# Project_Canary_V4_3.net
KiCad netlist of a schematic drawn in EAGLE
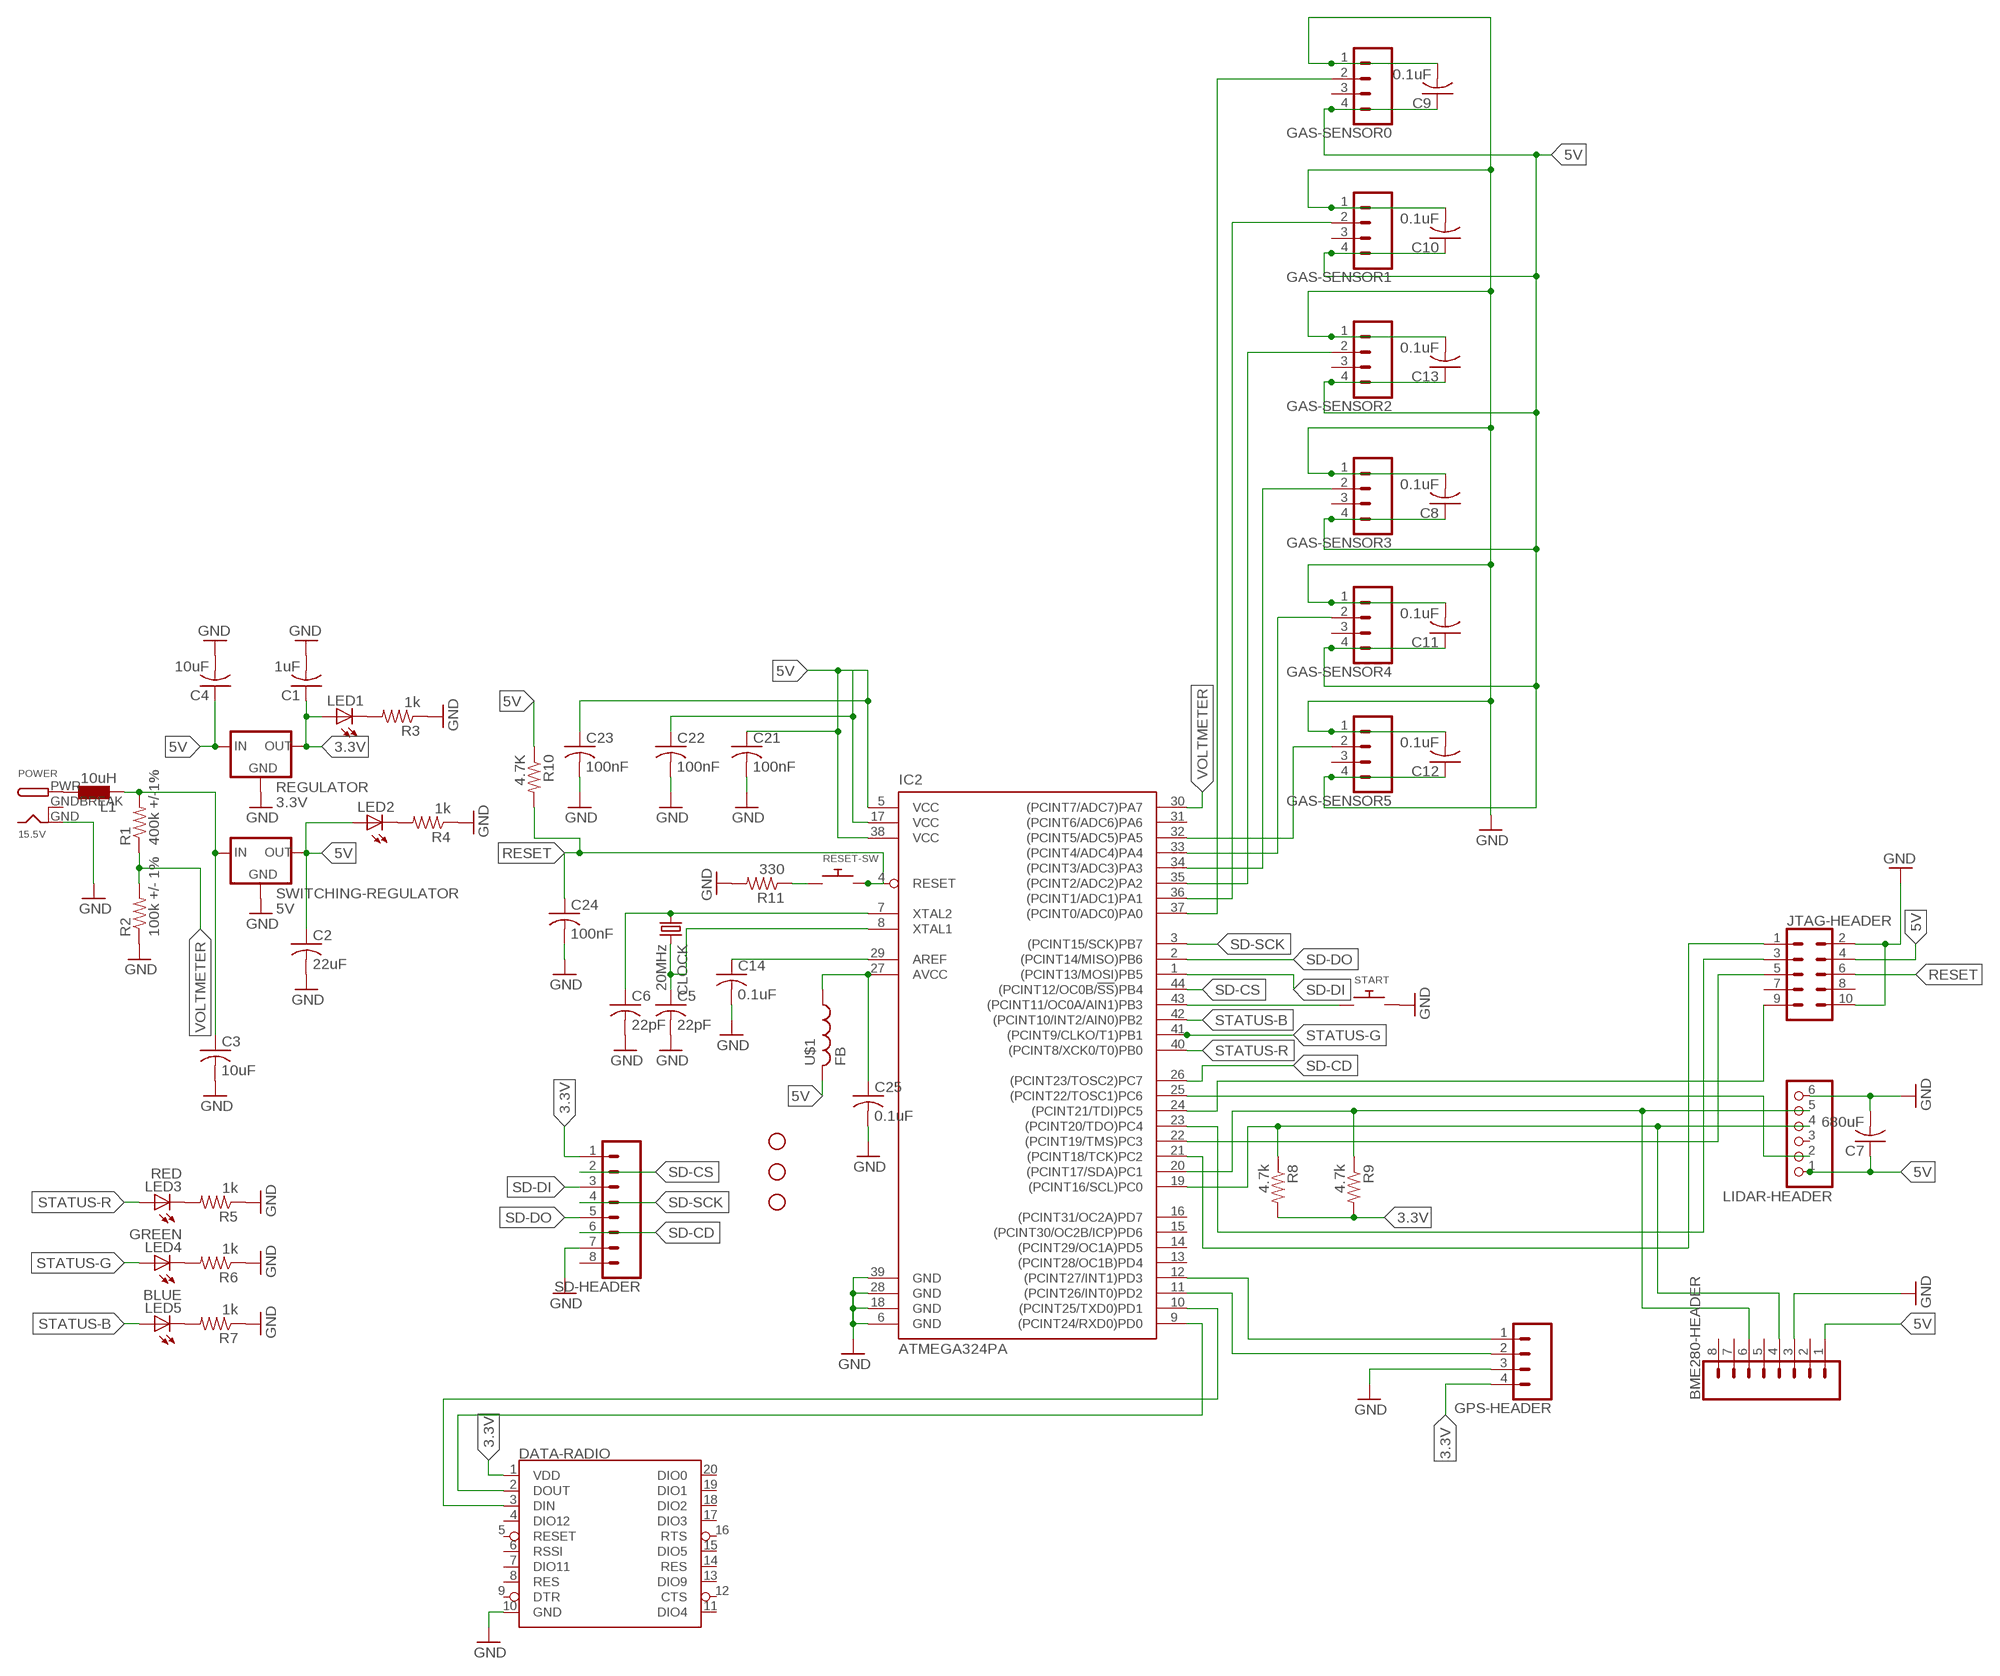
[diagram p0: schematic, sheet 1]

(export (version "E")
  (design (tool "Eeschema 10.0.6"))
  (components
    (comp (ref "BME280-HEADER")
      (value "CONN_08\"")
      (footprint "eagle-import:1X08")
      (libsource (lib "eagle-import") (part "CONN_08{dblquote}"))
    )
    (comp (ref "C1")
      (value "1uF")
      (footprint "eagle-import:C0805")
      (libsource (lib "eagle-import") (part "C-USC0805"))
    )
    (comp (ref "C2")
      (value "22uF")
      (footprint "eagle-import:C0603")
      (libsource (lib "eagle-import") (part "C-USC0603"))
    )
    (comp (ref "C3")
      (value "10uF")
      (footprint "eagle-import:C0805")
      (libsource (lib "eagle-import") (part "C-USC0805"))
    )
    (comp (ref "C4")
      (value "10uF")
      (footprint "eagle-import:C0603")
      (libsource (lib "eagle-import") (part "C-USC0603"))
    )
    (comp (ref "C5")
      (value "22pF")
      (footprint "eagle-import:C0603")
      (libsource (lib "eagle-import") (part "C-USC0603"))
    )
    (comp (ref "C6")
      (value "22pF")
      (footprint "eagle-import:C0603")
      (libsource (lib "eagle-import") (part "C-USC0603"))
    )
    (comp (ref "C7")
      (value "680uF")
      (footprint "eagle-import:C0603")
      (libsource (lib "eagle-import") (part "C-USC0603"))
    )
    (comp (ref "C8")
      (value "0.1uF")
      (footprint "eagle-import:C0603")
      (libsource (lib "eagle-import") (part "C-USC0603"))
    )
    (comp (ref "C9")
      (value "0.1uF")
      (footprint "eagle-import:C0603")
      (libsource (lib "eagle-import") (part "C-USC0603"))
    )
    (comp (ref "C10")
      (value "0.1uF")
      (footprint "eagle-import:C0603")
      (libsource (lib "eagle-import") (part "C-USC0603"))
    )
    (comp (ref "C11")
      (value "0.1uF")
      (footprint "eagle-import:C0603")
      (libsource (lib "eagle-import") (part "C-USC0603"))
    )
    (comp (ref "C12")
      (value "0.1uF")
      (footprint "eagle-import:C0603")
      (libsource (lib "eagle-import") (part "C-USC0603"))
    )
    (comp (ref "C13")
      (value "0.1uF")
      (footprint "eagle-import:C0603")
      (libsource (lib "eagle-import") (part "C-USC0603"))
    )
    (comp (ref "C14")
      (value "0.1uF")
      (footprint "eagle-import:C0603")
      (libsource (lib "eagle-import") (part "C-USC0603"))
    )
    (comp (ref "C21")
      (value "100nF")
      (footprint "eagle-import:C0603")
      (libsource (lib "eagle-import") (part "C-USC0603"))
    )
    (comp (ref "C22")
      (value "100nF")
      (footprint "eagle-import:C0603")
      (libsource (lib "eagle-import") (part "C-USC0603"))
    )
    (comp (ref "C23")
      (value "100nF")
      (footprint "eagle-import:C0603")
      (libsource (lib "eagle-import") (part "C-USC0603"))
    )
    (comp (ref "C24")
      (value "100nF")
      (footprint "eagle-import:C0805")
      (libsource (lib "eagle-import") (part "C-USC0805"))
    )
    (comp (ref "C25")
      (value "0.1uF")
      (footprint "eagle-import:C0603")
      (libsource (lib "eagle-import") (part "C-USC0603"))
    )
    (comp (ref "CLOCK")
      (value "20MHz")
      (footprint "eagle-import:86SMX")
      (libsource (lib "eagle-import") (part "CRYSTAL68SMX"))
    )
    (comp (ref "DATA-RADIO")
      (value "XBEE")
      (footprint "eagle-import:XBEE")
      (libsource (lib "eagle-import") (part "XBEE"))
    )
    (comp (ref "GAS-SENSOR0")
      (value "CONN_04")
      (footprint "eagle-import:1X04")
      (libsource (lib "eagle-import") (part "CONN_04"))
    )
    (comp (ref "GAS-SENSOR1")
      (value "CONN_04")
      (footprint "eagle-import:1X04")
      (libsource (lib "eagle-import") (part "CONN_04"))
    )
    (comp (ref "GAS-SENSOR2")
      (value "CONN_04")
      (footprint "eagle-import:1X04")
      (libsource (lib "eagle-import") (part "CONN_04"))
    )
    (comp (ref "GAS-SENSOR3")
      (value "CONN_04")
      (footprint "eagle-import:1X04")
      (libsource (lib "eagle-import") (part "CONN_04"))
    )
    (comp (ref "GAS-SENSOR4")
      (value "CONN_04")
      (footprint "eagle-import:1X04")
      (libsource (lib "eagle-import") (part "CONN_04"))
    )
    (comp (ref "GAS-SENSOR5")
      (value "CONN_04")
      (footprint "eagle-import:1X04")
      (libsource (lib "eagle-import") (part "CONN_04"))
    )
    (comp (ref "GPS-HEADER")
      (value "CONN_04")
      (footprint "eagle-import:1X04")
      (libsource (lib "eagle-import") (part "CONN_04"))
    )
    (comp (ref "IC2")
      (value "ATMEGA324PA")
      (footprint "eagle-import:TQFP44")
      (fields (field (name "MPN") "ATMEGA644PV-10AU"))
      (libsource (lib "eagle-import") (part "ATMEGA644A"))
    )
    (comp (ref "JTAG-HEADER")
      (value "CONN_05X2PTH")
      (footprint "eagle-import:2X5")
      (libsource (lib "eagle-import") (part "CONN_05X2PTH"))
    )
    (comp (ref "L1")
      (value "10uH")
      (footprint "eagle-import:L1812")
      (libsource (lib "eagle-import") (part "L"))
    )
    (comp (ref "LED1")
      (value "LEDCHIP-LED0805")
      (footprint "eagle-import:CHIP-LED0805")
      (libsource (lib "eagle-import") (part "LEDCHIP-LED0805"))
    )
    (comp (ref "LED2")
      (value "LEDCHIP-LED0805")
      (footprint "eagle-import:CHIP-LED0805")
      (libsource (lib "eagle-import") (part "LEDCHIP-LED0805"))
    )
    (comp (ref "LED3")
      (value "RED")
      (footprint "eagle-import:CHIP-LED0805")
      (libsource (lib "eagle-import") (part "LEDCHIP-LED0805"))
    )
    (comp (ref "LED4")
      (value "GREEN")
      (footprint "eagle-import:CHIP-LED0805")
      (libsource (lib "eagle-import") (part "LEDCHIP-LED0805"))
    )
    (comp (ref "LED5")
      (value "BLUE")
      (footprint "eagle-import:CHIP-LED0805")
      (libsource (lib "eagle-import") (part "LEDCHIP-LED0805"))
    )
    (comp (ref "LIDAR-HEADER")
      (value "PINHD-1X6")
      (footprint "eagle-import:1X06")
      (libsource (lib "eagle-import") (part "PINHD-1X6"))
    )
    (comp (ref "MOUNT-HOLE1")
      (value "STAND-OFF")
      (footprint "eagle-import:STAND-OFF")
      (libsource (lib "eagle-import") (part "STAND-OFF"))
    )
    (comp (ref "MOUNT-HOLE2")
      (value "STAND-OFF")
      (footprint "eagle-import:STAND-OFF")
      (libsource (lib "eagle-import") (part "STAND-OFF"))
    )
    (comp (ref "MOUNT-HOLE3")
      (value "STAND-OFF")
      (footprint "eagle-import:STAND-OFF")
      (libsource (lib "eagle-import") (part "STAND-OFF"))
    )
    (comp (ref "POWER")
      (value "15.5V")
      (footprint "eagle-import:DCJACK_2MM_PTH")
      (libsource (lib "eagle-import") (part "DCBARRELPTH"))
    )
    (comp (ref "R1")
      (value "400k +/-1%")
      (footprint "eagle-import:M0805")
      (libsource (lib "eagle-import") (part "R-US_M0805"))
    )
    (comp (ref "R2")
      (value "100k +/- 1%")
      (footprint "eagle-import:M0805")
      (libsource (lib "eagle-import") (part "R-US_M0805"))
    )
    (comp (ref "R3")
      (value "1k")
      (footprint "eagle-import:M0805")
      (libsource (lib "eagle-import") (part "R-US_M0805"))
    )
    (comp (ref "R4")
      (value "1k")
      (footprint "eagle-import:M0805")
      (libsource (lib "eagle-import") (part "R-US_M0805"))
    )
    (comp (ref "R5")
      (value "1k")
      (footprint "eagle-import:M0805")
      (libsource (lib "eagle-import") (part "R-US_M0805"))
    )
    (comp (ref "R6")
      (value "1k")
      (footprint "eagle-import:M0805")
      (libsource (lib "eagle-import") (part "R-US_M0805"))
    )
    (comp (ref "R7")
      (value "1k")
      (footprint "eagle-import:M0805")
      (libsource (lib "eagle-import") (part "R-US_M0805"))
    )
    (comp (ref "R8")
      (value "4.7k")
      (footprint "eagle-import:M0805")
      (libsource (lib "eagle-import") (part "R-US_M0805"))
    )
    (comp (ref "R9")
      (value "4.7k")
      (footprint "eagle-import:M0805")
      (libsource (lib "eagle-import") (part "R-US_M0805"))
    )
    (comp (ref "R10")
      (value "4.7K")
      (footprint "eagle-import:M0805")
      (libsource (lib "eagle-import") (part "R-US_M0805"))
    )
    (comp (ref "R11")
      (value "330")
      (footprint "eagle-import:M0805")
      (libsource (lib "eagle-import") (part "R-US_M0805"))
    )
    (comp (ref "REGULATOR")
      (value "3.3V")
      (footprint "eagle-import:TO220-IGO")
      (libsource (lib "eagle-import") (part "V_REG_78XXSINK"))
    )
    (comp (ref "RESET-SW")
      (value "SWITCH_PUSHBUTTONSOFTTOUCHSMD_SJ")
      (footprint "eagle-import:PUSHBUTTON_SMD_SJ")
      (libsource (lib "eagle-import") (part "SWITCH_PUSHBUTTONSOFTTOUCHSMD_SJ"))
    )
    (comp (ref "SD-HEADER")
      (value "CONN_08\"")
      (footprint "eagle-import:1X08")
      (libsource (lib "eagle-import") (part "CONN_08{dblquote}"))
    )
    (comp (ref "START")
      (value "SWITCH_PUSHBUTTONSOFTTOUCHSMD_SJ")
      (footprint "eagle-import:PUSHBUTTON_SMD_SJ")
      (libsource (lib "eagle-import") (part "SWITCH_PUSHBUTTONSOFTTOUCHSMD_SJ"))
    )
    (comp (ref "SWITCHING-REGULATOR")
      (value "5V")
      (footprint "eagle-import:TO220-IGO")
      (libsource (lib "eagle-import") (part "V_REG_78XXSINK"))
    )
    (comp (ref "U$1") (value "FB") (footprint "eagle-import:FB") (libsource (lib "eagle-import") (part "FB")))
  )
  (nets
    (net (code "1") (name "/GNDBREAK") (class "Default")
      (node (ref "POWER") (pin "GNDBREAK") (pinfunction "GNDBREAK_GNDBREAK") (pintype "power_in"))
    )
    (net (code "2") (name "3.3V") (class "Default")
      (node (ref "C1") (pin "1") (pinfunction "1_1") (pintype "passive"))
      (node (ref "DATA-RADIO") (pin "1") (pinfunction "VDD_1") (pintype "power_in"))
      (node (ref "GPS-HEADER") (pin "4") (pinfunction "4_4") (pintype "passive"))
      (node (ref "LED1") (pin "A") (pinfunction "A_A") (pintype "passive"))
      (node (ref "R8") (pin "2") (pinfunction "2_2") (pintype "passive"))
      (node (ref "R9") (pin "2") (pinfunction "2_2") (pintype "passive"))
      (node (ref "REGULATOR") (pin "OUT") (pinfunction "OUT_OUT") (pintype "passive"))
      (node (ref "SD-HEADER") (pin "1") (pinfunction "1_1") (pintype "passive"))
    )
    (net (code "3") (name "5V") (class "Default")
      (node (ref "BME280-HEADER") (pin "1") (pinfunction "1_1") (pintype "passive"))
      (node (ref "C10") (pin "1") (pinfunction "1_1") (pintype "passive"))
      (node (ref "C11") (pin "1") (pinfunction "1_1") (pintype "passive"))
      (node (ref "C12") (pin "1") (pinfunction "1_1") (pintype "passive"))
      (node (ref "C13") (pin "1") (pinfunction "1_1") (pintype "passive"))
      (node (ref "C2") (pin "1") (pinfunction "1_1") (pintype "passive"))
      (node (ref "C21") (pin "1") (pinfunction "1_1") (pintype "passive"))
      (node (ref "C22") (pin "1") (pinfunction "1_1") (pintype "passive"))
      (node (ref "C23") (pin "1") (pinfunction "1_1") (pintype "passive"))
      (node (ref "C25") (pin "1") (pinfunction "1_1") (pintype "passive"))
      (node (ref "C4") (pin "1") (pinfunction "1_1") (pintype "passive"))
      (node (ref "C7") (pin "1") (pinfunction "1_1") (pintype "passive"))
      (node (ref "C8") (pin "1") (pinfunction "1_1") (pintype "passive"))
      (node (ref "C9") (pin "1") (pinfunction "1_1") (pintype "passive"))
      (node (ref "GAS-SENSOR0") (pin "4") (pinfunction "4_4") (pintype "passive"))
      (node (ref "GAS-SENSOR1") (pin "4") (pinfunction "4_4") (pintype "passive"))
      (node (ref "GAS-SENSOR2") (pin "4") (pinfunction "4_4") (pintype "passive"))
      (node (ref "GAS-SENSOR3") (pin "4") (pinfunction "4_4") (pintype "passive"))
      (node (ref "GAS-SENSOR4") (pin "4") (pinfunction "4_4") (pintype "passive"))
      (node (ref "GAS-SENSOR5") (pin "4") (pinfunction "4_4") (pintype "passive"))
      (node (ref "IC2") (pin "17") (pinfunction "VCC_17") (pintype "power_in"))
      (node (ref "IC2") (pin "27") (pinfunction "AVCC_27") (pintype "power_in"))
      (node (ref "IC2") (pin "38") (pinfunction "VCC_38") (pintype "power_in"))
      (node (ref "IC2") (pin "5") (pinfunction "VCC_5") (pintype "power_in"))
      (node (ref "JTAG-HEADER") (pin "4") (pinfunction "4_4") (pintype "passive"))
      (node (ref "LED2") (pin "A") (pinfunction "A_A") (pintype "passive"))
      (node (ref "LIDAR-HEADER") (pin "1") (pinfunction "1_1") (pintype "passive"))
      (node (ref "REGULATOR") (pin "IN") (pinfunction "IN_IN") (pintype "input"))
      (node (ref "SWITCHING-REGULATOR") (pin "OUT") (pinfunction "OUT_OUT") (pintype "passive"))
      (node (ref "U$1") (pin "P$1") (pinfunction "1_P$1") (pintype "passive"))
    )
    (net (code "4") (name "GND") (class "Default")
      (node (ref "BME280-HEADER") (pin "3") (pinfunction "3_3") (pintype "passive"))
      (node (ref "C1") (pin "2") (pinfunction "2_2") (pintype "passive"))
      (node (ref "C10") (pin "2") (pinfunction "2_2") (pintype "passive"))
      (node (ref "C11") (pin "2") (pinfunction "2_2") (pintype "passive"))
      (node (ref "C12") (pin "2") (pinfunction "2_2") (pintype "passive"))
      (node (ref "C13") (pin "2") (pinfunction "2_2") (pintype "passive"))
      (node (ref "C14") (pin "2") (pinfunction "2_2") (pintype "passive"))
      (node (ref "C2") (pin "2") (pinfunction "2_2") (pintype "passive"))
      (node (ref "C21") (pin "2") (pinfunction "2_2") (pintype "passive"))
      (node (ref "C22") (pin "2") (pinfunction "2_2") (pintype "passive"))
      (node (ref "C23") (pin "2") (pinfunction "2_2") (pintype "passive"))
      (node (ref "C24") (pin "2") (pinfunction "2_2") (pintype "passive"))
      (node (ref "C25") (pin "2") (pinfunction "2_2") (pintype "passive"))
      (node (ref "C3") (pin "2") (pinfunction "2_2") (pintype "passive"))
      (node (ref "C4") (pin "2") (pinfunction "2_2") (pintype "passive"))
      (node (ref "C5") (pin "2") (pinfunction "2_2") (pintype "passive"))
      (node (ref "C6") (pin "2") (pinfunction "2_2") (pintype "passive"))
      (node (ref "C7") (pin "2") (pinfunction "2_2") (pintype "passive"))
      (node (ref "C8") (pin "2") (pinfunction "2_2") (pintype "passive"))
      (node (ref "C9") (pin "2") (pinfunction "2_2") (pintype "passive"))
      (node (ref "DATA-RADIO") (pin "10") (pinfunction "GND_10") (pintype "power_in"))
      (node (ref "GAS-SENSOR0") (pin "1") (pinfunction "1_1") (pintype "passive"))
      (node (ref "GAS-SENSOR1") (pin "1") (pinfunction "1_1") (pintype "passive"))
      (node (ref "GAS-SENSOR2") (pin "1") (pinfunction "1_1") (pintype "passive"))
      (node (ref "GAS-SENSOR3") (pin "1") (pinfunction "1_1") (pintype "passive"))
      (node (ref "GAS-SENSOR4") (pin "1") (pinfunction "1_1") (pintype "passive"))
      (node (ref "GAS-SENSOR5") (pin "1") (pinfunction "1_1") (pintype "passive"))
      (node (ref "GPS-HEADER") (pin "3") (pinfunction "3_3") (pintype "passive"))
      (node (ref "IC2") (pin "18") (pinfunction "GND_18") (pintype "power_in"))
      (node (ref "IC2") (pin "28") (pinfunction "GND_28") (pintype "power_in"))
      (node (ref "IC2") (pin "39") (pinfunction "GND_39") (pintype "power_in"))
      (node (ref "IC2") (pin "6") (pinfunction "GND_6") (pintype "power_in"))
      (node (ref "JTAG-HEADER") (pin "10") (pinfunction "10_10") (pintype "passive"))
      (node (ref "JTAG-HEADER") (pin "2") (pinfunction "2_2") (pintype "passive"))
      (node (ref "LIDAR-HEADER") (pin "6") (pinfunction "6_6") (pintype "passive"))
      (node (ref "POWER") (pin "GND") (pinfunction "GND_GND") (pintype "power_in"))
      (node (ref "R11") (pin "2") (pinfunction "2_2") (pintype "passive"))
      (node (ref "R2") (pin "1") (pinfunction "1_1") (pintype "passive"))
      (node (ref "R3") (pin "1") (pinfunction "1_1") (pintype "passive"))
      (node (ref "R4") (pin "1") (pinfunction "1_1") (pintype "passive"))
      (node (ref "R5") (pin "1") (pinfunction "1_1") (pintype "passive"))
      (node (ref "R6") (pin "1") (pinfunction "1_1") (pintype "passive"))
      (node (ref "R7") (pin "1") (pinfunction "1_1") (pintype "passive"))
      (node (ref "REGULATOR") (pin "GND") (pinfunction "GND_GND") (pintype "input"))
      (node (ref "SD-HEADER") (pin "7") (pinfunction "7_7") (pintype "passive"))
      (node (ref "START") (pin "P$2") (pinfunction "P$2_P$2") (pintype "passive"))
      (node (ref "SWITCHING-REGULATOR") (pin "GND") (pinfunction "GND_GND") (pintype "input"))
    )
    (net (code "5") (name "Net-(C3-Pad1)") (class "Default")
      (node (ref "C3") (pin "1") (pinfunction "1_1") (pintype "passive"))
      (node (ref "L1") (pin "2") (pinfunction "2_2") (pintype "passive"))
      (node (ref "R1") (pin "2") (pinfunction "2_2") (pintype "passive"))
      (node (ref "SWITCHING-REGULATOR") (pin "IN") (pinfunction "IN_IN") (pintype "input"))
    )
    (net (code "6") (name "Net-(CLOCK-2)") (class "Default")
      (node (ref "C5") (pin "1") (pinfunction "1_1") (pintype "passive"))
      (node (ref "CLOCK") (pin "4") (pinfunction "2_4") (pintype "passive"))
      (node (ref "IC2") (pin "8") (pinfunction "XTAL1_8") (pintype "bidirectional"))
    )
    (net (code "7") (name "Net-(DATA-RADIO-DIN)") (class "Default")
      (node (ref "DATA-RADIO") (pin "3") (pinfunction "DIN_3") (pintype "input"))
      (node (ref "IC2") (pin "10") (pinfunction "(PCINT25/TXD0)PD1_10") (pintype "bidirectional"))
    )
    (net (code "8") (name "Net-(DATA-RADIO-DOUT)") (class "Default")
      (node (ref "DATA-RADIO") (pin "2") (pinfunction "DOUT_2") (pintype "output"))
      (node (ref "IC2") (pin "9") (pinfunction "(PCINT24/RXD0)PD0_9") (pintype "bidirectional"))
    )
    (net (code "9") (name "Net-(IC2-(PCINT0{slash}ADC0)PA0)") (class "Default")
      (node (ref "GAS-SENSOR0") (pin "2") (pinfunction "2_2") (pintype "passive"))
      (node (ref "IC2") (pin "37") (pinfunction "(PCINT0/ADC0)PA0_37") (pintype "bidirectional"))
    )
    (net (code "10") (name "Net-(IC2-(PCINT1{slash}ADC1)PA1)") (class "Default")
      (node (ref "GAS-SENSOR1") (pin "2") (pinfunction "2_2") (pintype "passive"))
      (node (ref "IC2") (pin "36") (pinfunction "(PCINT1/ADC1)PA1_36") (pintype "bidirectional"))
    )
    (net (code "11") (name "Net-(IC2-(PCINT2{slash}ADC2)PA2)") (class "Default")
      (node (ref "GAS-SENSOR2") (pin "2") (pinfunction "2_2") (pintype "passive"))
      (node (ref "IC2") (pin "35") (pinfunction "(PCINT2/ADC2)PA2_35") (pintype "bidirectional"))
    )
    (net (code "12") (name "Net-(IC2-(PCINT3{slash}ADC3)PA3)") (class "Default")
      (node (ref "GAS-SENSOR3") (pin "2") (pinfunction "2_2") (pintype "passive"))
      (node (ref "IC2") (pin "34") (pinfunction "(PCINT3/ADC3)PA3_34") (pintype "bidirectional"))
    )
    (net (code "13") (name "Net-(IC2-(PCINT4{slash}ADC4)PA4)") (class "Default")
      (node (ref "GAS-SENSOR4") (pin "2") (pinfunction "2_2") (pintype "passive"))
      (node (ref "IC2") (pin "33") (pinfunction "(PCINT4/ADC4)PA4_33") (pintype "bidirectional"))
    )
    (net (code "14") (name "Net-(IC2-(PCINT5{slash}ADC5)PA5)") (class "Default")
      (node (ref "GAS-SENSOR5") (pin "2") (pinfunction "2_2") (pintype "passive"))
      (node (ref "IC2") (pin "32") (pinfunction "(PCINT5/ADC5)PA5_32") (pintype "bidirectional"))
    )
    (net (code "15") (name "Net-(IC2-(PCINT11{slash}OC0A{slash}AIN1)PB3)") (class "Default")
      (node (ref "IC2") (pin "43") (pinfunction "(PCINT11/OC0A/AIN1)PB3_43") (pintype "bidirectional"))
      (node (ref "START") (pin "P$1") (pinfunction "P$1_P$1") (pintype "passive"))
    )
    (net (code "16") (name "Net-(IC2-(PCINT16{slash}SCL)PC0)") (class "Default")
      (node (ref "BME280-HEADER") (pin "4") (pinfunction "4_4") (pintype "passive"))
      (node (ref "IC2") (pin "19") (pinfunction "(PCINT16/SCL)PC0_19") (pintype "output"))
      (node (ref "LIDAR-HEADER") (pin "4") (pinfunction "4_4") (pintype "passive"))
      (node (ref "R8") (pin "1") (pinfunction "1_1") (pintype "passive"))
    )
    (net (code "17") (name "Net-(IC2-(PCINT17{slash}SDA)PC1)") (class "Default")
      (node (ref "BME280-HEADER") (pin "6") (pinfunction "6_6") (pintype "passive"))
      (node (ref "IC2") (pin "20") (pinfunction "(PCINT17/SDA)PC1_20") (pintype "output"))
      (node (ref "LIDAR-HEADER") (pin "5") (pinfunction "5_5") (pintype "passive"))
      (node (ref "R9") (pin "1") (pinfunction "1_1") (pintype "passive"))
    )
    (net (code "18") (name "Net-(IC2-(PCINT18{slash}TCK)PC2)") (class "Default")
      (node (ref "IC2") (pin "21") (pinfunction "(PCINT18/TCK)PC2_21") (pintype "output"))
      (node (ref "JTAG-HEADER") (pin "1") (pinfunction "1_1") (pintype "passive"))
    )
    (net (code "19") (name "Net-(IC2-(PCINT19{slash}TMS)PC3)") (class "Default")
      (node (ref "IC2") (pin "22") (pinfunction "(PCINT19/TMS)PC3_22") (pintype "output"))
      (node (ref "JTAG-HEADER") (pin "5") (pinfunction "5_5") (pintype "passive"))
    )
    (net (code "20") (name "Net-(IC2-(PCINT20{slash}TDO)PC4)") (class "Default")
      (node (ref "IC2") (pin "23") (pinfunction "(PCINT20/TDO)PC4_23") (pintype "output"))
      (node (ref "JTAG-HEADER") (pin "3") (pinfunction "3_3") (pintype "passive"))
    )
    (net (code "21") (name "Net-(IC2-(PCINT21{slash}TDI)PC5)") (class "Default")
      (node (ref "IC2") (pin "24") (pinfunction "(PCINT21/TDI)PC5_24") (pintype "output"))
      (node (ref "JTAG-HEADER") (pin "9") (pinfunction "9_9") (pintype "passive"))
    )
    (net (code "22") (name "Net-(IC2-(PCINT22{slash}TOSC1)PC6)") (class "Default")
      (node (ref "IC2") (pin "25") (pinfunction "(PCINT22/TOSC1)PC6_25") (pintype "output"))
      (node (ref "LIDAR-HEADER") (pin "2") (pinfunction "2_2") (pintype "passive"))
    )
    (net (code "23") (name "Net-(IC2-(PCINT26{slash}INT0)PD2)") (class "Default")
      (node (ref "GPS-HEADER") (pin "2") (pinfunction "2_2") (pintype "passive"))
      (node (ref "IC2") (pin "11") (pinfunction "(PCINT26/INT0)PD2_11") (pintype "bidirectional"))
    )
    (net (code "24") (name "Net-(IC2-(PCINT27{slash}INT1)PD3)") (class "Default")
      (node (ref "GPS-HEADER") (pin "1") (pinfunction "1_1") (pintype "passive"))
      (node (ref "IC2") (pin "12") (pinfunction "(PCINT27/INT1)PD3_12") (pintype "bidirectional"))
    )
    (net (code "25") (name "Net-(IC2-AREF)") (class "Default")
      (node (ref "C14") (pin "1") (pinfunction "1_1") (pintype "passive"))
      (node (ref "IC2") (pin "29") (pinfunction "AREF_29") (pintype "passive"))
    )
    (net (code "26") (name "Net-(IC2-XTAL2)") (class "Default")
      (node (ref "C6") (pin "1") (pinfunction "1_1") (pintype "passive"))
      (node (ref "CLOCK") (pin "1") (pinfunction "1_1") (pintype "passive"))
      (node (ref "IC2") (pin "7") (pinfunction "XTAL2_7") (pintype "bidirectional"))
    )
    (net (code "27") (name "Net-(L1-Pad1)") (class "Default")
      (node (ref "L1") (pin "1") (pinfunction "1_1") (pintype "passive"))
      (node (ref "POWER") (pin "PWR") (pinfunction "PWR_PWR") (pintype "power_in"))
    )
    (net (code "28") (name "Net-(LED1-PadC)") (class "Default")
      (node (ref "LED1") (pin "C") (pinfunction "C_C") (pintype "passive"))
      (node (ref "R3") (pin "2") (pinfunction "2_2") (pintype "passive"))
    )
    (net (code "29") (name "Net-(LED2-PadC)") (class "Default")
      (node (ref "LED2") (pin "C") (pinfunction "C_C") (pintype "passive"))
      (node (ref "R4") (pin "2") (pinfunction "2_2") (pintype "passive"))
    )
    (net (code "30") (name "Net-(LED3-PadC)") (class "Default")
      (node (ref "LED3") (pin "C") (pinfunction "C_C") (pintype "passive"))
      (node (ref "R5") (pin "2") (pinfunction "2_2") (pintype "passive"))
    )
    (net (code "31") (name "Net-(LED4-PadC)") (class "Default")
      (node (ref "LED4") (pin "C") (pinfunction "C_C") (pintype "passive"))
      (node (ref "R6") (pin "2") (pinfunction "2_2") (pintype "passive"))
    )
    (net (code "32") (name "Net-(LED5-PadC)") (class "Default")
      (node (ref "LED5") (pin "C") (pinfunction "C_C") (pintype "passive"))
      (node (ref "R7") (pin "2") (pinfunction "2_2") (pintype "passive"))
    )
    (net (code "33") (name "Net-(R11-Pad1)") (class "Default")
      (node (ref "R11") (pin "1") (pinfunction "1_1") (pintype "passive"))
      (node (ref "RESET-SW") (pin "P$1") (pinfunction "P$1_P$1") (pintype "passive"))
    )
    (net (code "34") (name "RESET") (class "Default")
      (node (ref "C24") (pin "1") (pinfunction "1_1") (pintype "passive"))
      (node (ref "IC2") (pin "4") (pinfunction "RESET_4") (pintype "input"))
      (node (ref "JTAG-HEADER") (pin "6") (pinfunction "6_6") (pintype "passive"))
      (node (ref "R10") (pin "2") (pinfunction "2_2") (pintype "passive"))
      (node (ref "RESET-SW") (pin "P$2") (pinfunction "P$2_P$2") (pintype "passive"))
    )
    (net (code "35") (name "SD-CD") (class "Default")
      (node (ref "IC2") (pin "26") (pinfunction "(PCINT23/TOSC2)PC7_26") (pintype "output"))
      (node (ref "SD-HEADER") (pin "6") (pinfunction "6_6") (pintype "passive"))
    )
    (net (code "36") (name "SD-CS") (class "Default")
      (node (ref "IC2") (pin "44") (pinfunction "(PCINT12/OC0B/~{SS})PB4_44") (pintype "bidirectional"))
      (node (ref "SD-HEADER") (pin "2") (pinfunction "2_2") (pintype "passive"))
    )
    (net (code "37") (name "SD-DI") (class "Default")
      (node (ref "IC2") (pin "1") (pinfunction "(PCINT13/MOSI)PB5_1") (pintype "bidirectional"))
      (node (ref "SD-HEADER") (pin "3") (pinfunction "3_3") (pintype "passive"))
    )
    (net (code "38") (name "SD-DO") (class "Default")
      (node (ref "IC2") (pin "2") (pinfunction "(PCINT14/MISO)PB6_2") (pintype "bidirectional"))
      (node (ref "SD-HEADER") (pin "5") (pinfunction "5_5") (pintype "passive"))
    )
    (net (code "39") (name "SD-SCK") (class "Default")
      (node (ref "IC2") (pin "3") (pinfunction "(PCINT15/SCK)PB7_3") (pintype "bidirectional"))
      (node (ref "SD-HEADER") (pin "4") (pinfunction "4_4") (pintype "passive"))
    )
    (net (code "40") (name "STATUS-B") (class "Default")
      (node (ref "IC2") (pin "42") (pinfunction "(PCINT10/INT2/AIN0)PB2_42") (pintype "bidirectional"))
      (node (ref "LED5") (pin "A") (pinfunction "A_A") (pintype "passive"))
    )
    (net (code "41") (name "STATUS-G") (class "Default")
      (node (ref "IC2") (pin "41") (pinfunction "(PCINT9/CLKO/T1)PB1_41") (pintype "bidirectional"))
      (node (ref "LED4") (pin "A") (pinfunction "A_A") (pintype "passive"))
    )
    (net (code "42") (name "STATUS-R") (class "Default")
      (node (ref "IC2") (pin "40") (pinfunction "(PCINT8/XCK0/T0)PB0_40") (pintype "bidirectional"))
      (node (ref "LED3") (pin "A") (pinfunction "A_A") (pintype "passive"))
    )
    (net (code "43") (name "VOLTMETER") (class "Default")
      (node (ref "IC2") (pin "30") (pinfunction "(PCINT7/ADC7)PA7_30") (pintype "bidirectional"))
      (node (ref "R1") (pin "1") (pinfunction "1_1") (pintype "passive"))
      (node (ref "R2") (pin "2") (pinfunction "2_2") (pintype "passive"))
    )
    (net (code "44") (name "unconnected-(BME280-HEADER-Pad2)") (class "Default")
      (node (ref "BME280-HEADER") (pin "2") (pinfunction "2_2") (pintype "passive"))
    )
    (net (code "45") (name "unconnected-(BME280-HEADER-Pad5)") (class "Default")
      (node (ref "BME280-HEADER") (pin "5") (pinfunction "5_5") (pintype "passive"))
    )
    (net (code "46") (name "unconnected-(BME280-HEADER-Pad7)") (class "Default")
      (node (ref "BME280-HEADER") (pin "7") (pinfunction "7_7") (pintype "passive"))
    )
    (net (code "47") (name "unconnected-(BME280-HEADER-Pad8)") (class "Default")
      (node (ref "BME280-HEADER") (pin "8") (pinfunction "8_8") (pintype "passive"))
    )
    (net (code "48") (name "unconnected-(DATA-RADIO-CTS-Pad12)") (class "Default")
      (node (ref "DATA-RADIO") (pin "12") (pinfunction "CTS_12") (pintype "output"))
    )
    (net (code "49") (name "unconnected-(DATA-RADIO-DIO0-Pad20)") (class "Default")
      (node (ref "DATA-RADIO") (pin "20") (pinfunction "DIO0_20") (pintype "bidirectional"))
    )
    (net (code "50") (name "unconnected-(DATA-RADIO-DIO1-Pad19)") (class "Default")
      (node (ref "DATA-RADIO") (pin "19") (pinfunction "DIO1_19") (pintype "bidirectional"))
    )
    (net (code "51") (name "unconnected-(DATA-RADIO-DIO2-Pad18)") (class "Default")
      (node (ref "DATA-RADIO") (pin "18") (pinfunction "DIO2_18") (pintype "bidirectional"))
    )
    (net (code "52") (name "unconnected-(DATA-RADIO-DIO3-Pad17)") (class "Default")
      (node (ref "DATA-RADIO") (pin "17") (pinfunction "DIO3_17") (pintype "bidirectional"))
    )
    (net (code "53") (name "unconnected-(DATA-RADIO-DIO4-Pad11)") (class "Default")
      (node (ref "DATA-RADIO") (pin "11") (pinfunction "DIO4_11") (pintype "bidirectional"))
    )
    (net (code "54") (name "unconnected-(DATA-RADIO-DIO5-Pad15)") (class "Default")
      (node (ref "DATA-RADIO") (pin "15") (pinfunction "DIO5_15") (pintype "bidirectional"))
    )
    (net (code "55") (name "unconnected-(DATA-RADIO-DIO9-Pad13)") (class "Default")
      (node (ref "DATA-RADIO") (pin "13") (pinfunction "DIO9_13") (pintype "bidirectional"))
    )
    (net (code "56") (name "unconnected-(DATA-RADIO-DIO11-Pad7)") (class "Default")
      (node (ref "DATA-RADIO") (pin "7") (pinfunction "DIO11_7") (pintype "bidirectional"))
    )
    (net (code "57") (name "unconnected-(DATA-RADIO-DIO12-Pad4)") (class "Default")
      (node (ref "DATA-RADIO") (pin "4") (pinfunction "DIO12_4") (pintype "bidirectional"))
    )
    (net (code "58") (name "unconnected-(DATA-RADIO-DTR-Pad9)") (class "Default")
      (node (ref "DATA-RADIO") (pin "9") (pinfunction "DTR_9") (pintype "bidirectional"))
    )
    (net (code "59") (name "unconnected-(DATA-RADIO-RES-Pad8)") (class "Default")
      (node (ref "DATA-RADIO") (pin "8") (pinfunction "RES_8") (pintype "bidirectional"))
    )
    (net (code "60") (name "unconnected-(DATA-RADIO-RES-Pad14)") (class "Default")
      (node (ref "DATA-RADIO") (pin "14") (pinfunction "RES_14") (pintype "bidirectional"))
    )
    (net (code "61") (name "unconnected-(DATA-RADIO-RESET-Pad5)") (class "Default")
      (node (ref "DATA-RADIO") (pin "5") (pinfunction "RESET_5") (pintype "input"))
    )
    (net (code "62") (name "unconnected-(DATA-RADIO-RSSI-Pad6)") (class "Default")
      (node (ref "DATA-RADIO") (pin "6") (pinfunction "RSSI_6") (pintype "bidirectional"))
    )
    (net (code "63") (name "unconnected-(DATA-RADIO-RTS-Pad16)") (class "Default")
      (node (ref "DATA-RADIO") (pin "16") (pinfunction "RTS_16") (pintype "input"))
    )
    (net (code "64") (name "unconnected-(GAS-SENSOR0-Pad3)") (class "Default")
      (node (ref "GAS-SENSOR0") (pin "3") (pinfunction "3_3") (pintype "passive"))
    )
    (net (code "65") (name "unconnected-(GAS-SENSOR1-Pad3)") (class "Default")
      (node (ref "GAS-SENSOR1") (pin "3") (pinfunction "3_3") (pintype "passive"))
    )
    (net (code "66") (name "unconnected-(GAS-SENSOR2-Pad3)") (class "Default")
      (node (ref "GAS-SENSOR2") (pin "3") (pinfunction "3_3") (pintype "passive"))
    )
    (net (code "67") (name "unconnected-(GAS-SENSOR3-Pad3)") (class "Default")
      (node (ref "GAS-SENSOR3") (pin "3") (pinfunction "3_3") (pintype "passive"))
    )
    (net (code "68") (name "unconnected-(GAS-SENSOR4-Pad3)") (class "Default")
      (node (ref "GAS-SENSOR4") (pin "3") (pinfunction "3_3") (pintype "passive"))
    )
    (net (code "69") (name "unconnected-(GAS-SENSOR5-Pad3)") (class "Default")
      (node (ref "GAS-SENSOR5") (pin "3") (pinfunction "3_3") (pintype "passive"))
    )
    (net (code "70") (name "unconnected-(IC2-(PCINT6{slash}ADC6)PA6-Pad31)") (class "Default")
      (node (ref "IC2") (pin "31") (pinfunction "(PCINT6/ADC6)PA6_31") (pintype "bidirectional"))
    )
    (net (code "71") (name "unconnected-(IC2-(PCINT28{slash}OC1B)PD4-Pad13)") (class "Default")
      (node (ref "IC2") (pin "13") (pinfunction "(PCINT28/OC1B)PD4_13") (pintype "bidirectional"))
    )
    (net (code "72") (name "unconnected-(IC2-(PCINT29{slash}OC1A)PD5-Pad14)") (class "Default")
      (node (ref "IC2") (pin "14") (pinfunction "(PCINT29/OC1A)PD5_14") (pintype "bidirectional"))
    )
    (net (code "73") (name "unconnected-(IC2-(PCINT30{slash}OC2B{slash}ICP)PD6-Pad15)") (class "Default")
      (node (ref "IC2") (pin "15") (pinfunction "(PCINT30/OC2B/ICP)PD6_15") (pintype "bidirectional"))
    )
    (net (code "74") (name "unconnected-(IC2-(PCINT31{slash}OC2A)PD7-Pad16)") (class "Default")
      (node (ref "IC2") (pin "16") (pinfunction "(PCINT31/OC2A)PD7_16") (pintype "bidirectional"))
    )
    (net (code "75") (name "unconnected-(JTAG-HEADER-Pad7)") (class "Default")
      (node (ref "JTAG-HEADER") (pin "7") (pinfunction "7_7") (pintype "passive"))
    )
    (net (code "76") (name "unconnected-(JTAG-HEADER-Pad8)") (class "Default")
      (node (ref "JTAG-HEADER") (pin "8") (pinfunction "8_8") (pintype "passive"))
    )
    (net (code "77") (name "unconnected-(LIDAR-HEADER-Pad3)") (class "Default")
      (node (ref "LIDAR-HEADER") (pin "3") (pinfunction "3_3") (pintype "passive"))
    )
    (net (code "78") (name "unconnected-(R10-Pad1)") (class "Default")
      (node (ref "R10") (pin "1") (pinfunction "1_1") (pintype "passive"))
    )
    (net (code "79") (name "unconnected-(SD-HEADER-Pad8)") (class "Default")
      (node (ref "SD-HEADER") (pin "8") (pinfunction "8_8") (pintype "passive"))
    )
    (net (code "80") (name "unconnected-(U$1-2-PadP$2)") (class "Default")
      (node (ref "U$1") (pin "P$2") (pinfunction "2_P$2") (pintype "passive"))
    )
  )
)
